# Boost_stage_power_stage.net
KiCad netlist of a schematic drawn in Altium Designer
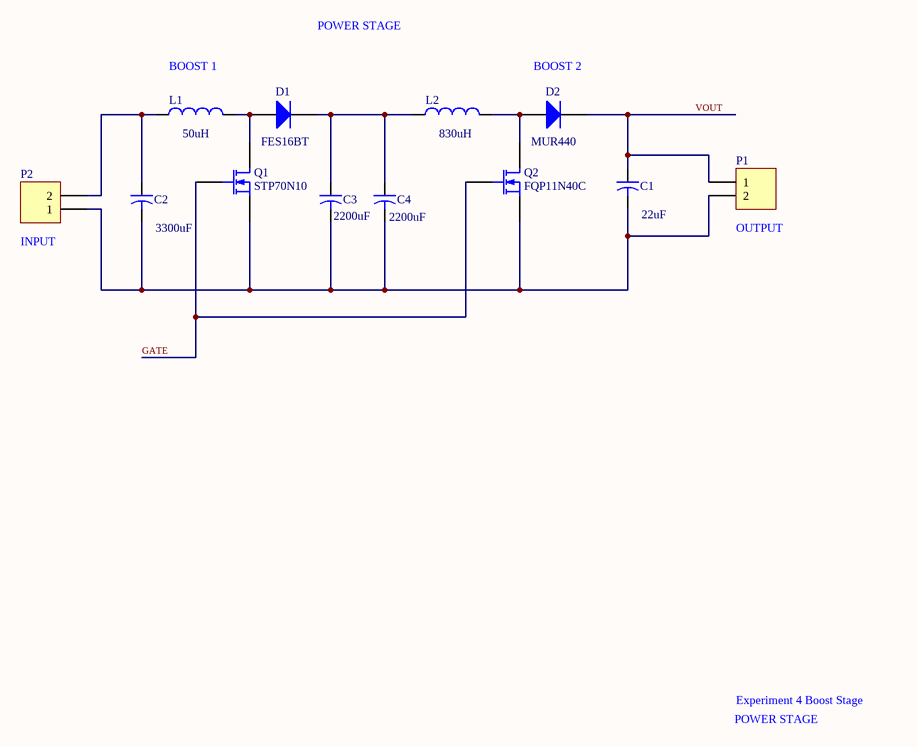
[diagram p0: Boost_stage_power_stage.SchDoc]

(export (version "E")
  (design (tool "Eeschema 10.0.6"))
  (components
    (comp (ref "C1")
      (value "22uF")
      (footprint "CAPR5-4X5")
      (description "Capacitor")
      (fields (field (name "Comment") "Cap2") (field (name "PUBLISHER") "Altium Limited"))
      (libsource (lib "Miscellaneous Devices") (part "Cap2"))
    )
    (comp (ref "C2")
      (value "3300uF")
      (footprint "CAPR5-4X5")
      (description "Capacitor")
      (fields (field (name "Comment") "Cap2") (field (name "PUBLISHER") "Altium Limited"))
      (libsource (lib "Miscellaneous Devices") (part "Cap2"))
    )
    (comp (ref "C3")
      (value "2200uF")
      (footprint "CAPR5-4X5")
      (description "Capacitor")
      (fields (field (name "Comment") "Cap2") (field (name "PUBLISHER") "Altium Limited"))
      (libsource (lib "Miscellaneous Devices") (part "Cap2"))
    )
    (comp (ref "C4")
      (value "2200uF")
      (footprint "CAPR5-4X5")
      (description "Capacitor")
      (fields (field (name "Comment") "Cap2") (field (name "PUBLISHER") "Altium Limited"))
      (libsource (lib "Miscellaneous Devices") (part "Cap2"))
    )
    (comp (ref "D1")
      (value "FES16BT")
      (footprint "SMC")
      (description "Default Diode")
      (fields (field (name "PUBLISHER") "Altium Limited"))
      (libsource (lib "Miscellaneous Devices") (part "Diode"))
    )
    (comp (ref "D2")
      (value "MUR440")
      (footprint "SMC")
      (description "Default Diode")
      (fields (field (name "PUBLISHER") "Altium Limited"))
      (libsource (lib "Miscellaneous Devices") (part "Diode"))
    )
    (comp (ref "L1")
      (value "50uH")
      (footprint "0402-A")
      (description "Inductor")
      (fields (field (name "PUBLISHER") "Altium Limited"))
      (libsource (lib "Miscellaneous Devices") (part "Inductor"))
    )
    (comp (ref "L2")
      (value "830uH")
      (footprint "0402-A")
      (description "Inductor")
      (fields (field (name "PUBLISHER") "Altium Limited"))
      (libsource (lib "Miscellaneous Devices") (part "Inductor"))
    )
    (comp (ref "P1")
      (value "Header 2")
      (footprint "HDR1X2")
      (description "Header, 2-Pin")
      (fields (field (name "PUBLISHER") "Altium Limited"))
      (libsource (lib "") (part "Header 2_1"))
    )
    (comp (ref "P2")
      (value "Header 2")
      (footprint "HDR1X2")
      (description "Header, 2-Pin")
      (fields (field (name "PUBLISHER") "Altium Limited"))
      (libsource (lib "Miscellaneous Connectors") (part "Header 2"))
    )
    (comp (ref "Q1")
      (value "STP70N10")
      (footprint "E3")
      (description "N-Channel MOSFET")
      (fields (field (name "PUBLISHER") "Altium Limited"))
      (libsource (lib "Miscellaneous Devices") (part "MOSFET-N"))
    )
    (comp (ref "Q2")
      (value "FQP11N40C")
      (footprint "E3")
      (description "N-Channel MOSFET")
      (fields (field (name "PUBLISHER") "Altium Limited"))
      (libsource (lib "Miscellaneous Devices") (part "MOSFET-N"))
    )
  )
  (nets
    (net (code "1") (name "/GATE") (class "Default")
      (node (ref "Q1") (pin "2") (pinfunction "G_2") (pintype "passive"))
      (node (ref "Q2") (pin "2") (pinfunction "G_2") (pintype "passive"))
    )
    (net (code "2") (name "/VOUT") (class "Default")
      (node (ref "C1") (pin "1") (pinfunction "1_1") (pintype "passive"))
      (node (ref "D2") (pin "2") (pinfunction "K_2") (pintype "passive"))
      (node (ref "P1") (pin "1") (pinfunction "1_1") (pintype "passive"))
    )
    (net (code "3") (name "Net-(C2-Pad1)") (class "Default")
      (node (ref "C2") (pin "1") (pinfunction "1_1") (pintype "passive"))
      (node (ref "L1") (pin "1") (pinfunction "1_1") (pintype "passive"))
      (node (ref "P2") (pin "2") (pinfunction "2_2") (pintype "passive"))
    )
    (net (code "4") (name "Net-(D1-A)") (class "Default")
      (node (ref "D1") (pin "1") (pinfunction "A_1") (pintype "passive"))
      (node (ref "L1") (pin "2") (pinfunction "2_2") (pintype "passive"))
      (node (ref "Q1") (pin "1") (pinfunction "D_1") (pintype "passive"))
    )
    (net (code "5") (name "Net-(D1-K)") (class "Default")
      (node (ref "C3") (pin "1") (pinfunction "1_1") (pintype "passive"))
      (node (ref "C4") (pin "1") (pinfunction "1_1") (pintype "passive"))
      (node (ref "D1") (pin "2") (pinfunction "K_2") (pintype "passive"))
      (node (ref "L2") (pin "1") (pinfunction "1_1") (pintype "passive"))
    )
    (net (code "6") (name "Net-(D2-A)") (class "Default")
      (node (ref "D2") (pin "1") (pinfunction "A_1") (pintype "passive"))
      (node (ref "L2") (pin "2") (pinfunction "2_2") (pintype "passive"))
      (node (ref "Q2") (pin "1") (pinfunction "D_1") (pintype "passive"))
    )
    (net (code "7") (name "Net-(Q1-S)") (class "Default")
      (node (ref "C1") (pin "2") (pinfunction "2_2") (pintype "passive"))
      (node (ref "C2") (pin "2") (pinfunction "2_2") (pintype "passive"))
      (node (ref "C3") (pin "2") (pinfunction "2_2") (pintype "passive"))
      (node (ref "C4") (pin "2") (pinfunction "2_2") (pintype "passive"))
      (node (ref "P1") (pin "2") (pinfunction "2_2") (pintype "passive"))
      (node (ref "P2") (pin "1") (pinfunction "1_1") (pintype "passive"))
      (node (ref "Q1") (pin "3") (pinfunction "S_3") (pintype "passive"))
      (node (ref "Q2") (pin "3") (pinfunction "S_3") (pintype "passive"))
    )
  )
)
